# Schematic.net
KiCad netlist of a schematic drawn in EasyEDA
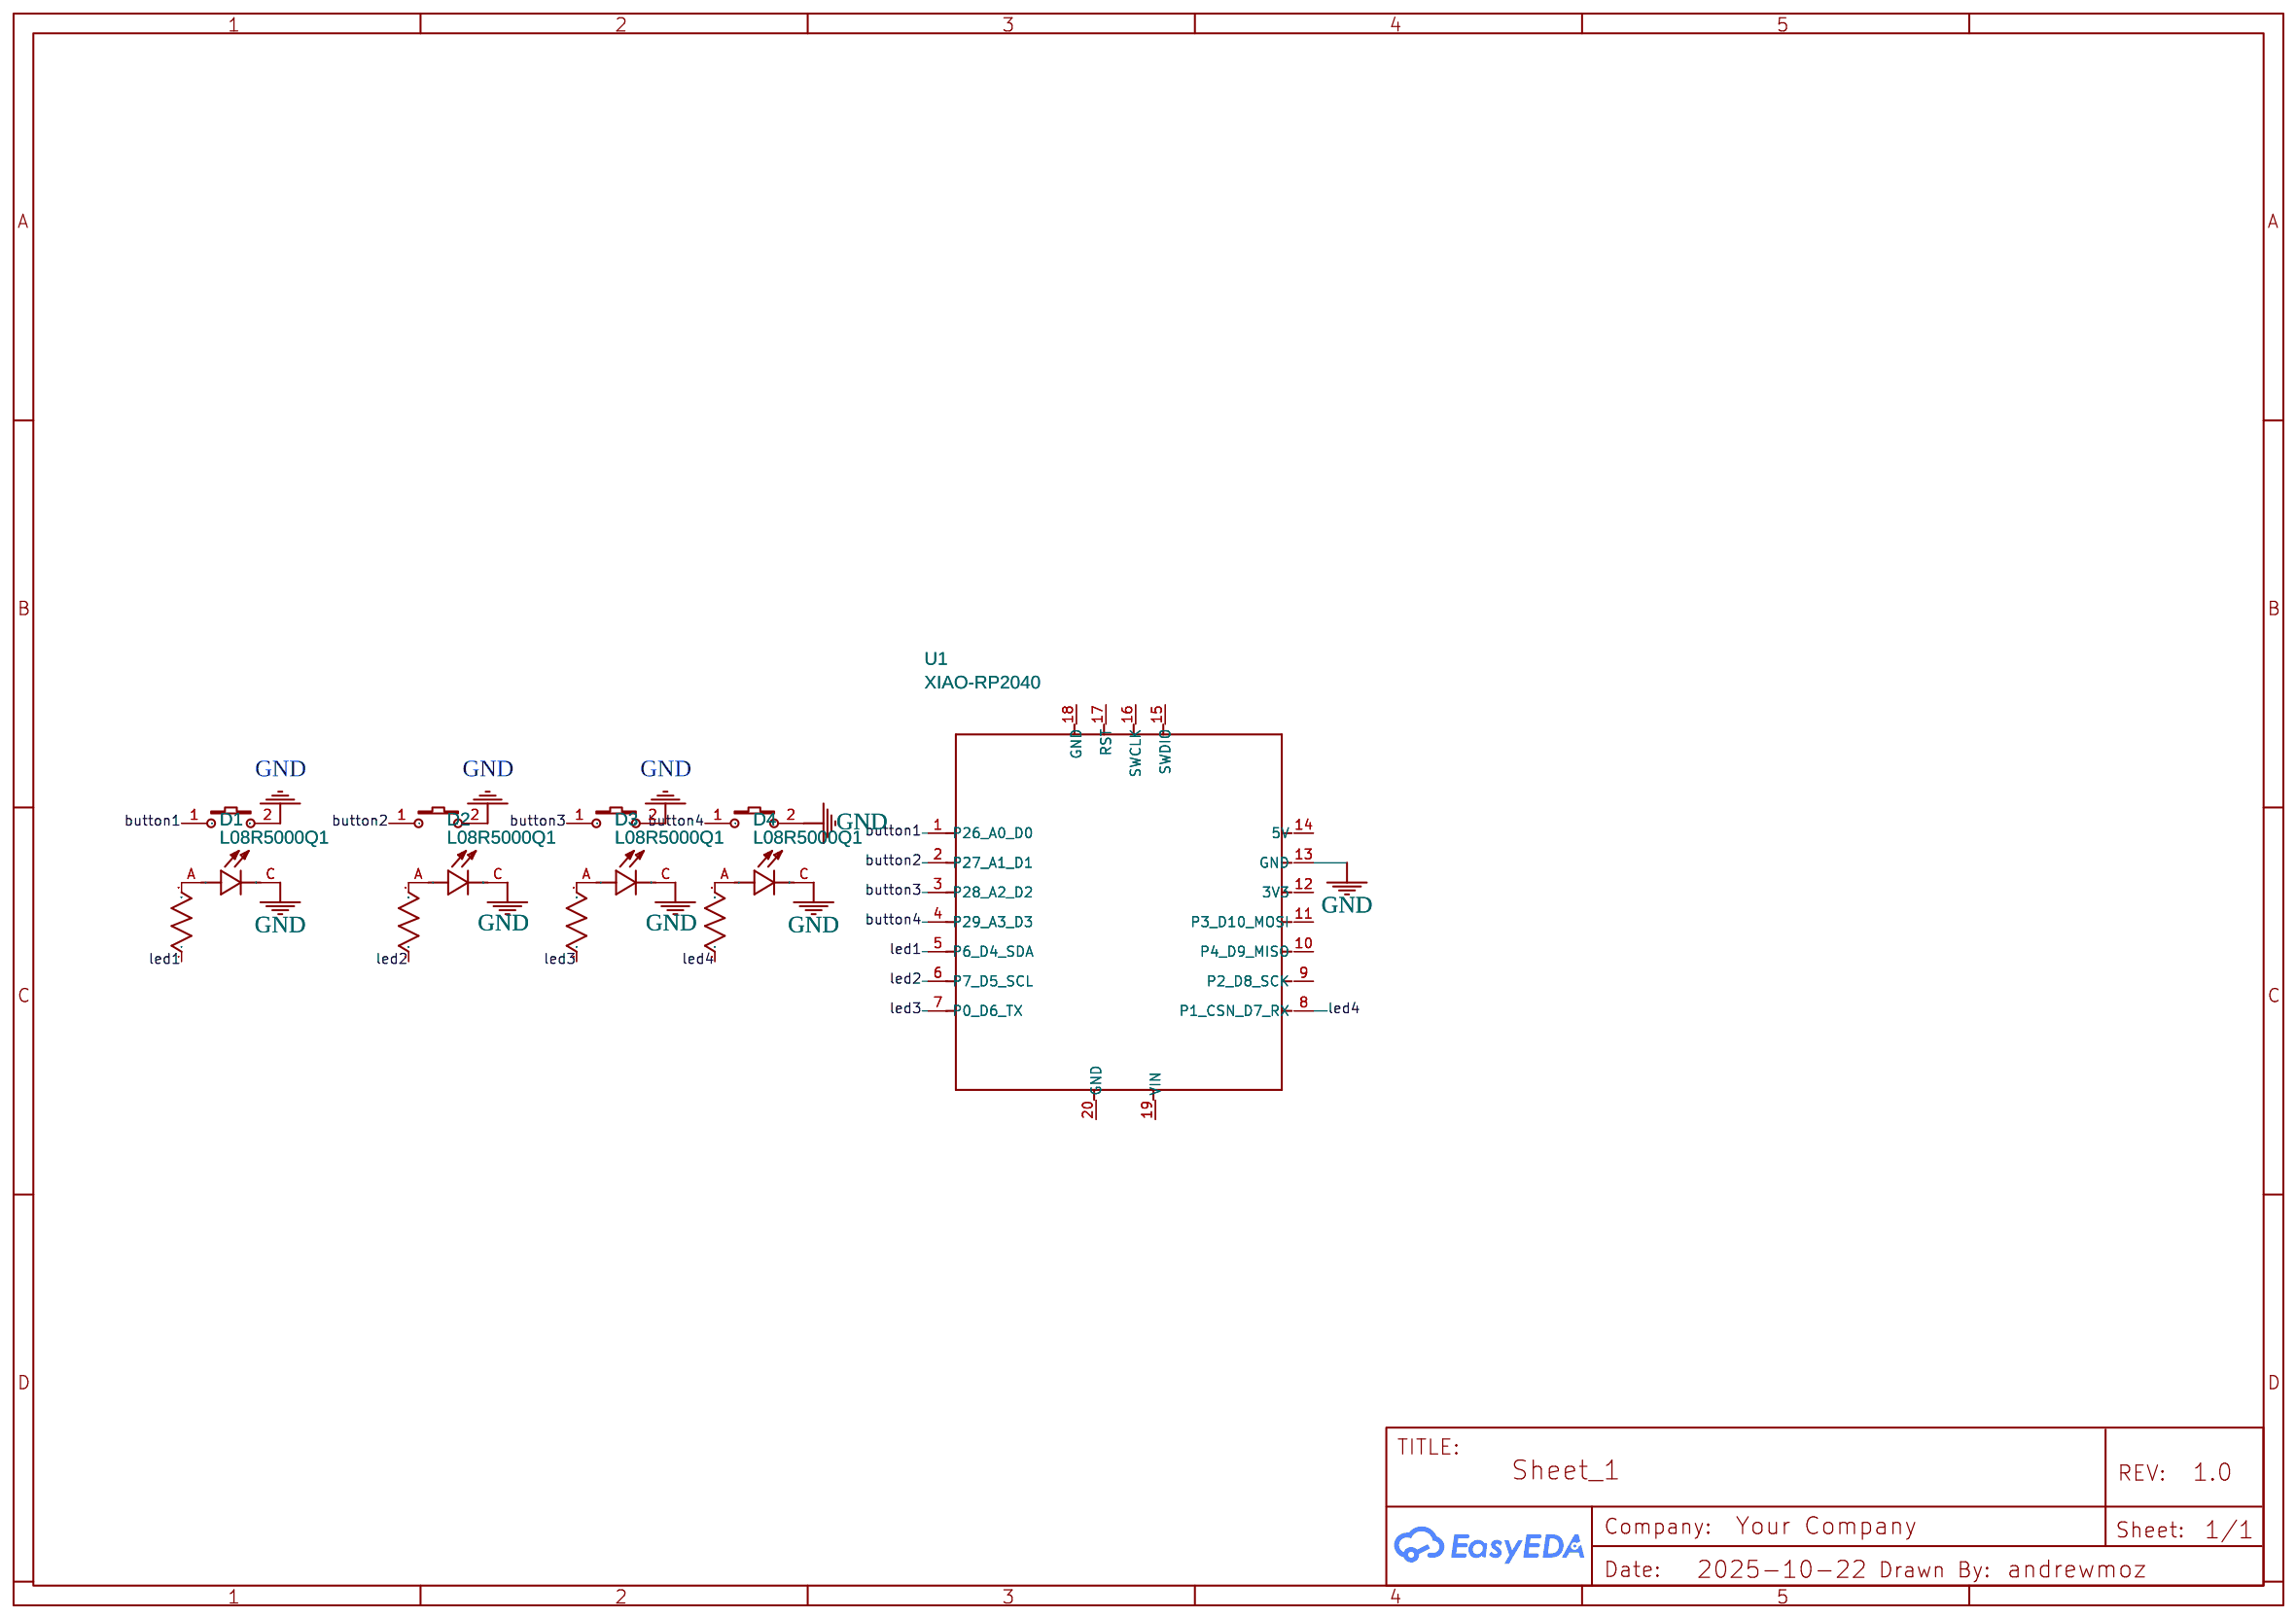
[diagram p0: schematic sheet]

(export (version "E")
  (design (tool "Eeschema 10.0.6"))
  (components
    (comp (ref "D1") (value "L08R5000Q1") (libsource (lib "") (part "L08R5000Q1")))
    (comp (ref "D2") (value "L08R5000Q1") (libsource (lib "") (part "L08R5000Q1")))
    (comp (ref "D3") (value "L08R5000Q1") (libsource (lib "") (part "L08R5000Q1")))
    (comp (ref "D4") (value "L08R5000Q1") (libsource (lib "") (part "L08R5000Q1")))
    (comp (ref "KEY1")
      (value "K2-3.6×6.1_SMD")
      (fields (field (name "Manufacturer Part") "K2-1107ST-A4SW-06"))
      (libsource (lib "") (part "K2-3.6×6.1_SMD"))
    )
    (comp (ref "KEY2")
      (value "K2-3.6×6.1_SMD")
      (fields (field (name "Manufacturer Part") "K2-1107ST-A4SW-06"))
      (libsource (lib "") (part "K2-3.6×6.1_SMD"))
    )
    (comp (ref "KEY3")
      (value "K2-3.6×6.1_SMD")
      (fields (field (name "Manufacturer Part") "K2-1107ST-A4SW-06"))
      (libsource (lib "") (part "K2-3.6×6.1_SMD"))
    )
    (comp (ref "KEY4")
      (value "K2-3.6×6.1_SMD")
      (fields (field (name "Manufacturer Part") "K2-1107ST-A4SW-06"))
      (libsource (lib "") (part "K2-3.6×6.1_SMD"))
    )
    (comp (ref "R1") (value "1k") (libsource (lib "") (part "R_0603_US")))
    (comp (ref "R2") (value "1k") (libsource (lib "") (part "R_0603_US")))
    (comp (ref "R3") (value "1k") (libsource (lib "") (part "R_0603_US")))
    (comp (ref "R4") (value "1k") (libsource (lib "") (part "R_0603_US")))
    (comp (ref "U1") (value "XIAO-RP2040") (libsource (lib "") (part "XIAO-RP2040")))
  )
  (nets
    (net (code "1") (name "/button1") (class "Default")
      (node (ref "KEY3") (pin "1") (pinfunction "1_1") (pintype "unspecified"))
      (node (ref "U1") (pin "1") (pinfunction "P26_A0_D0_1") (pintype "bidirectional"))
    )
    (net (code "2") (name "/button2") (class "Default")
      (node (ref "KEY2") (pin "1") (pinfunction "1_1") (pintype "unspecified"))
      (node (ref "U1") (pin "2") (pinfunction "P27_A1_D1_2") (pintype "bidirectional"))
    )
    (net (code "3") (name "/button3") (class "Default")
      (node (ref "KEY1") (pin "1") (pinfunction "1_1") (pintype "unspecified"))
      (node (ref "U1") (pin "3") (pinfunction "P28_A2_D2_3") (pintype "bidirectional"))
    )
    (net (code "4") (name "/button4") (class "Default")
      (node (ref "KEY4") (pin "1") (pinfunction "1_1") (pintype "unspecified"))
      (node (ref "U1") (pin "4") (pinfunction "P29_A3_D3_4") (pintype "bidirectional"))
    )
    (net (code "5") (name "/led1") (class "Default")
      (node (ref "R1") (pin "1") (pinfunction "1_1") (pintype "unspecified"))
      (node (ref "U1") (pin "5") (pinfunction "P6_D4_SDA_5") (pintype "bidirectional"))
    )
    (net (code "6") (name "/led2") (class "Default")
      (node (ref "R2") (pin "1") (pinfunction "1_1") (pintype "unspecified"))
      (node (ref "U1") (pin "6") (pinfunction "P7_D5_SCL_6") (pintype "bidirectional"))
    )
    (net (code "7") (name "/led3") (class "Default")
      (node (ref "R3") (pin "1") (pinfunction "1_1") (pintype "unspecified"))
      (node (ref "U1") (pin "7") (pinfunction "P0_D6_TX_7") (pintype "bidirectional"))
    )
    (net (code "8") (name "/led4") (class "Default")
      (node (ref "R4") (pin "1") (pinfunction "1_1") (pintype "unspecified"))
      (node (ref "U1") (pin "8") (pinfunction "P1_CSN_D7_RX_8") (pintype "bidirectional"))
    )
    (net (code "9") (name "GND") (class "Default")
      (node (ref "D1") (pin "C") (pinfunction "C_C") (pintype "bidirectional"))
      (node (ref "D2") (pin "C") (pinfunction "C_C") (pintype "bidirectional"))
      (node (ref "D3") (pin "C") (pinfunction "C_C") (pintype "bidirectional"))
      (node (ref "D4") (pin "C") (pinfunction "C_C") (pintype "bidirectional"))
      (node (ref "KEY1") (pin "2") (pinfunction "2_2") (pintype "unspecified"))
      (node (ref "KEY2") (pin "2") (pinfunction "2_2") (pintype "unspecified"))
      (node (ref "KEY3") (pin "2") (pinfunction "2_2") (pintype "unspecified"))
      (node (ref "KEY4") (pin "2") (pinfunction "2_2") (pintype "unspecified"))
      (node (ref "U1") (pin "13") (pinfunction "GND_13") (pintype "bidirectional"))
    )
    (net (code "10") (name "Net-(D1-PadA)") (class "Default")
      (node (ref "D1") (pin "A") (pinfunction "A_A") (pintype "bidirectional"))
      (node (ref "R1") (pin "2") (pinfunction "2_2") (pintype "unspecified"))
    )
    (net (code "11") (name "Net-(D2-PadA)") (class "Default")
      (node (ref "D2") (pin "A") (pinfunction "A_A") (pintype "bidirectional"))
      (node (ref "R2") (pin "2") (pinfunction "2_2") (pintype "unspecified"))
    )
    (net (code "12") (name "Net-(D3-PadA)") (class "Default")
      (node (ref "D3") (pin "A") (pinfunction "A_A") (pintype "bidirectional"))
      (node (ref "R3") (pin "2") (pinfunction "2_2") (pintype "unspecified"))
    )
    (net (code "13") (name "Net-(D4-PadA)") (class "Default")
      (node (ref "D4") (pin "A") (pinfunction "A_A") (pintype "bidirectional"))
      (node (ref "R4") (pin "2") (pinfunction "2_2") (pintype "unspecified"))
    )
    (net (code "14") (name "unconnected-(U1-3V3-Pad12)") (class "Default")
      (node (ref "U1") (pin "12") (pinfunction "3V3_12") (pintype "bidirectional"))
    )
    (net (code "15") (name "unconnected-(U1-5V-Pad14)") (class "Default")
      (node (ref "U1") (pin "14") (pinfunction "5V_14") (pintype "bidirectional"))
    )
    (net (code "16") (name "unconnected-(U1-GND-Pad18)") (class "Default")
      (node (ref "U1") (pin "18") (pinfunction "GND_18") (pintype "bidirectional"))
    )
    (net (code "17") (name "unconnected-(U1-GND-Pad20)") (class "Default")
      (node (ref "U1") (pin "20") (pinfunction "GND_20") (pintype "bidirectional"))
    )
    (net (code "18") (name "unconnected-(U1-P2_D8_SCK-Pad9)") (class "Default")
      (node (ref "U1") (pin "9") (pinfunction "P2_D8_SCK_9") (pintype "bidirectional"))
    )
    (net (code "19") (name "unconnected-(U1-P3_D10_MOSI-Pad11)") (class "Default")
      (node (ref "U1") (pin "11") (pinfunction "P3_D10_MOSI_11") (pintype "bidirectional"))
    )
    (net (code "20") (name "unconnected-(U1-P4_D9_MISO-Pad10)") (class "Default")
      (node (ref "U1") (pin "10") (pinfunction "P4_D9_MISO_10") (pintype "bidirectional"))
    )
    (net (code "21") (name "unconnected-(U1-RST-Pad17)") (class "Default")
      (node (ref "U1") (pin "17") (pinfunction "RST_17") (pintype "bidirectional"))
    )
    (net (code "22") (name "unconnected-(U1-SWCLK-Pad16)") (class "Default")
      (node (ref "U1") (pin "16") (pinfunction "SWCLK_16") (pintype "bidirectional"))
    )
    (net (code "23") (name "unconnected-(U1-SWDIO-Pad15)") (class "Default")
      (node (ref "U1") (pin "15") (pinfunction "SWDIO_15") (pintype "bidirectional"))
    )
    (net (code "24") (name "unconnected-(U1-VIN-Pad19)") (class "Default")
      (node (ref "U1") (pin "19") (pinfunction "VIN_19") (pintype "bidirectional"))
    )
  )
)
